# reflow_oven.net
KiCad netlist of a schematic drawn in EAGLE
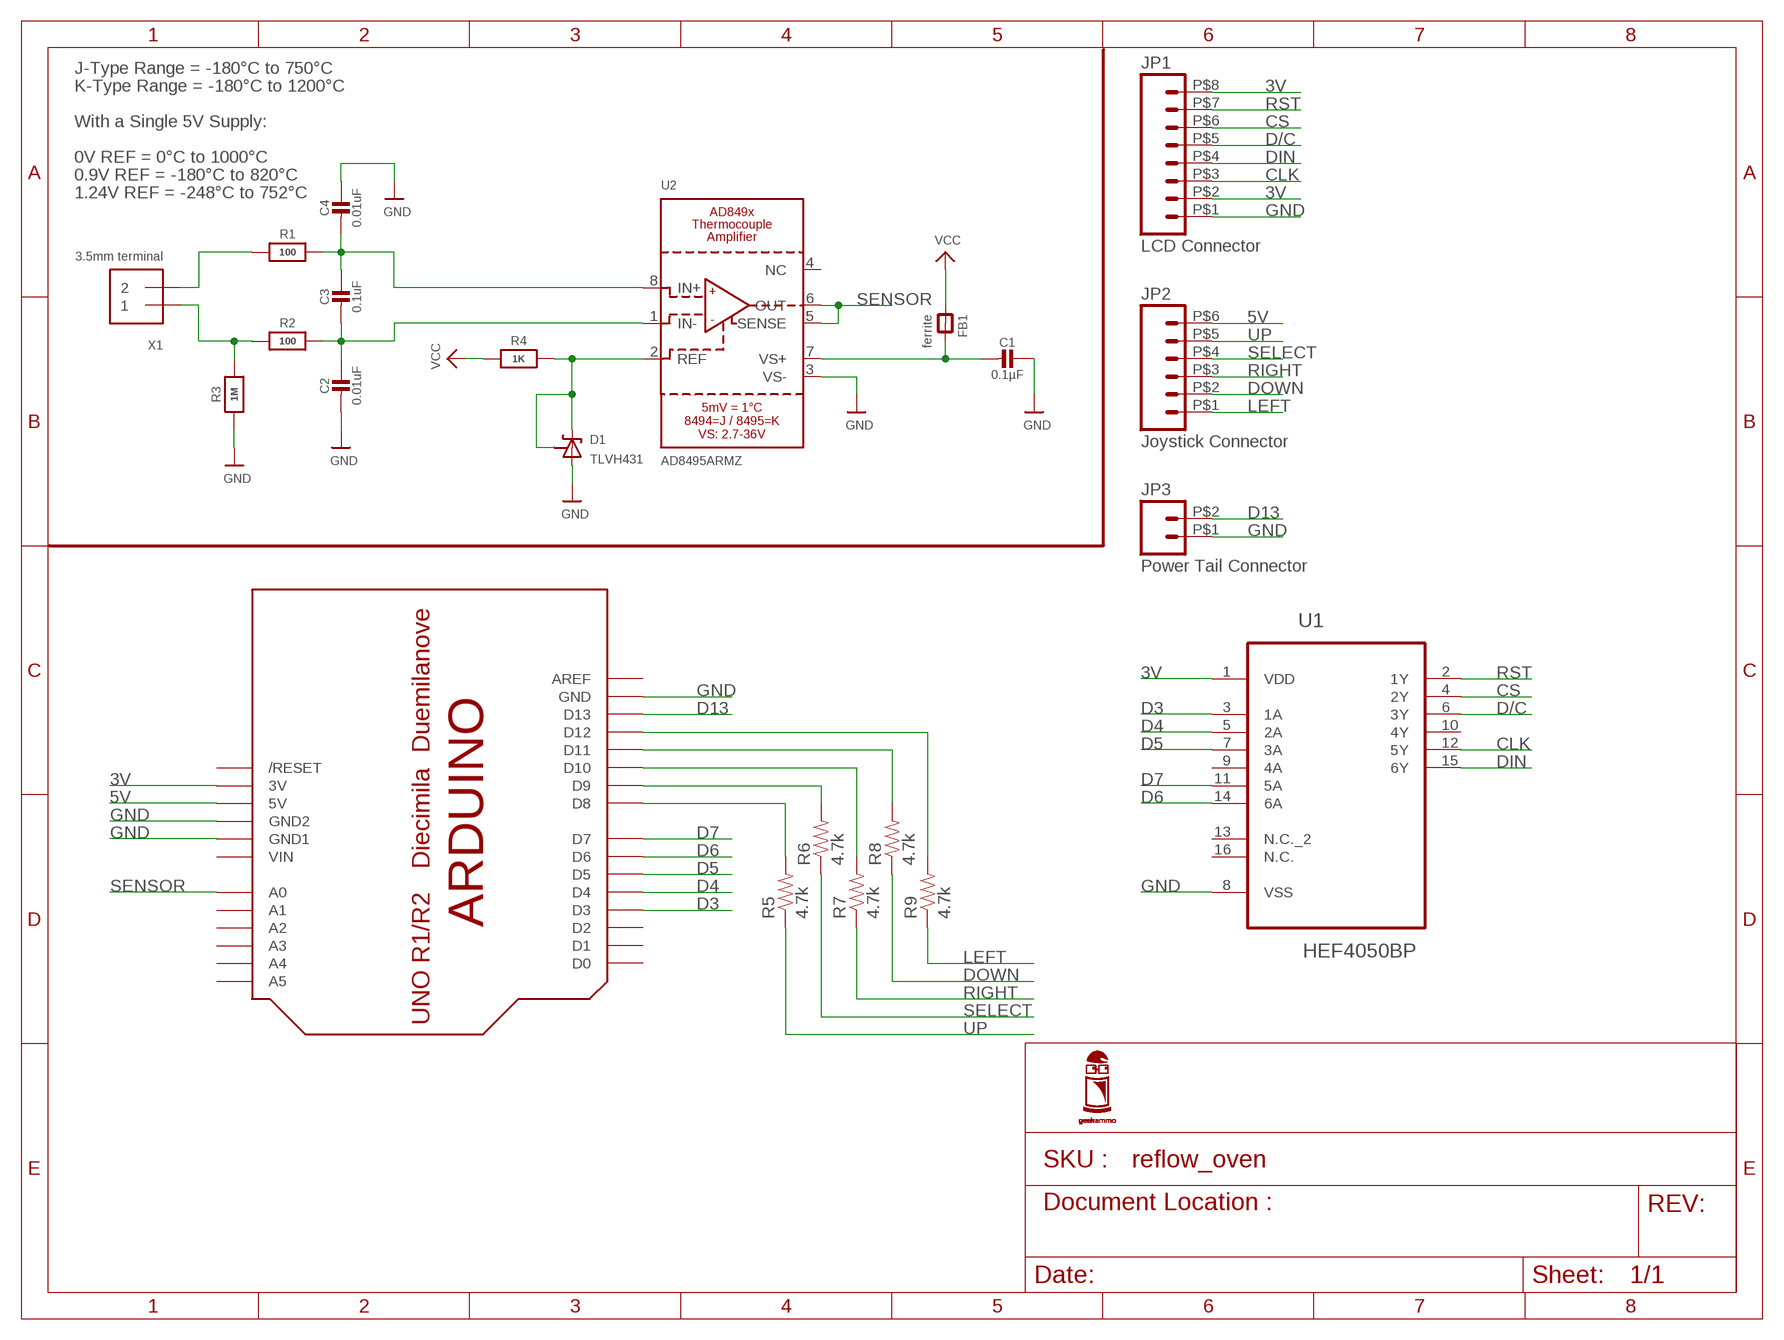
[diagram p0: schematic, sheet 1]

(export (version "E")
  (design (tool "Eeschema 10.0.6"))
  (components
    (comp (ref "C1")
      (value "0.1µF")
      (footprint "eagle-import:0805-NO")
      (libsource (lib "eagle-import") (part "CAP_CERAMIC0805-NOOUTLINE"))
    )
    (comp (ref "C2")
      (value "0.01uF")
      (footprint "eagle-import:0805-NO")
      (libsource (lib "eagle-import") (part "CAP_CERAMIC0805-NOOUTLINE"))
    )
    (comp (ref "C3")
      (value "0.1uF")
      (footprint "eagle-import:0805-NO")
      (libsource (lib "eagle-import") (part "CAP_CERAMIC0805-NOOUTLINE"))
    )
    (comp (ref "C4")
      (value "0.01uF")
      (footprint "eagle-import:0805-NO")
      (libsource (lib "eagle-import") (part "CAP_CERAMIC0805-NOOUTLINE"))
    )
    (comp (ref "D1")
      (value "TLVH431")
      (footprint "eagle-import:SOT23-R")
      (libsource (lib "eagle-import") (part "SHUNT-VREF"))
    )
    (comp (ref "FB1")
      (value "ferrite")
      (footprint "eagle-import:0805")
      (libsource (lib "eagle-import") (part "FERRITE0805"))
    )
    (comp (ref "JP1")
      (value "LCD Connector")
      (footprint "eagle-import:SPRINGTERMINAL-0.1_-8")
      (libsource (lib "eagle-import") (part "M080.1{dblquote}-8"))
    )
    (comp (ref "JP2")
      (value "Joystick Connector")
      (footprint "eagle-import:SPRINGTERMINAL-0.1_-6")
      (libsource (lib "eagle-import") (part "M06"))
    )
    (comp (ref "JP3")
      (value "Power Tail Connector")
      (footprint "eagle-import:SPRINGTERMINAL-0.1_-2")
      (libsource (lib "eagle-import") (part "M02SPRING-0.1{dblquote}"))
    )
    (comp (ref "R1")
      (value "100")
      (footprint "eagle-import:0805-NO")
      (libsource (lib "eagle-import") (part "RESISTOR0805_NOOUTLINE"))
    )
    (comp (ref "R2")
      (value "100")
      (footprint "eagle-import:0805-NO")
      (libsource (lib "eagle-import") (part "RESISTOR0805_NOOUTLINE"))
    )
    (comp (ref "R3")
      (value "1M")
      (footprint "eagle-import:0805-NO")
      (libsource (lib "eagle-import") (part "RESISTOR0805_NOOUTLINE"))
    )
    (comp (ref "R4")
      (value "1K")
      (footprint "eagle-import:0805-NO")
      (libsource (lib "eagle-import") (part "RESISTOR0805_NOOUTLINE"))
    )
    (comp (ref "R5")
      (value "4.7k")
      (footprint "eagle-import:0805")
      (libsource (lib "eagle-import") (part "RESISTOR0805-RES"))
    )
    (comp (ref "R6")
      (value "4.7k")
      (footprint "eagle-import:0805")
      (libsource (lib "eagle-import") (part "RESISTOR0805-RES"))
    )
    (comp (ref "R7")
      (value "4.7k")
      (footprint "eagle-import:0805")
      (libsource (lib "eagle-import") (part "RESISTOR0805-RES"))
    )
    (comp (ref "R8")
      (value "4.7k")
      (footprint "eagle-import:0805")
      (libsource (lib "eagle-import") (part "RESISTOR0805-RES"))
    )
    (comp (ref "R9")
      (value "4.7k")
      (footprint "eagle-import:0805")
      (libsource (lib "eagle-import") (part "RESISTOR0805-RES"))
    )
    (comp (ref "U$1")
      (value "ARDUINOUNO")
      (footprint "eagle-import:ARDUINO")
      (libsource (lib "eagle-import") (part "ARDUINOUNO"))
    )
    (comp (ref "U1")
      (value "HEF4050BP")
      (footprint "eagle-import:DIP254P762X420-16")
      (libsource (lib "eagle-import") (part "HEF4050BP"))
    )
    (comp (ref "U2")
      (value "AD8495ARMZ")
      (footprint "eagle-import:MSOP8_0.65MM")
      (libsource (lib "eagle-import") (part "AD849X"))
    )
    (comp (ref "X1")
      (value "3.5mm terminal")
      (footprint "eagle-import:TERMBLOCK_1X2-3.5MM")
      (libsource (lib "eagle-import") (part "TERMBLOCK_1X2"))
    )
  )
  (nets
    (net (code "1") (name "/3V") (class "Default")
      (node (ref "JP1") (pin "P$2") (pinfunction "2_P$2") (pintype "passive"))
      (node (ref "JP1") (pin "P$8") (pinfunction "8_P$8") (pintype "passive"))
      (node (ref "U$1") (pin "3V") (pinfunction "3V_3V") (pintype "power_in"))
      (node (ref "U1") (pin "1") (pinfunction "VDD_1") (pintype "power_in"))
    )
    (net (code "2") (name "/5V") (class "Default")
      (node (ref "JP2") (pin "P$6") (pinfunction "6_P$6") (pintype "passive"))
      (node (ref "U$1") (pin "5V") (pinfunction "5V_5V") (pintype "power_in"))
    )
    (net (code "3") (name "/CLK") (class "Default")
      (node (ref "JP1") (pin "P$3") (pinfunction "3_P$3") (pintype "passive"))
      (node (ref "U1") (pin "12") (pinfunction "5Y_12") (pintype "output"))
    )
    (net (code "4") (name "/CS") (class "Default")
      (node (ref "JP1") (pin "P$6") (pinfunction "6_P$6") (pintype "passive"))
      (node (ref "U1") (pin "4") (pinfunction "2Y_4") (pintype "output"))
    )
    (net (code "5") (name "/D3") (class "Default")
      (node (ref "U$1") (pin "D3") (pinfunction "D3_D3") (pintype "bidirectional"))
      (node (ref "U1") (pin "3") (pinfunction "1A_3") (pintype "input"))
    )
    (net (code "6") (name "/D4") (class "Default")
      (node (ref "U$1") (pin "D4") (pinfunction "D4_D4") (pintype "bidirectional"))
      (node (ref "U1") (pin "5") (pinfunction "2A_5") (pintype "input"))
    )
    (net (code "7") (name "/D5") (class "Default")
      (node (ref "U$1") (pin "D5") (pinfunction "D5_D5") (pintype "bidirectional"))
      (node (ref "U1") (pin "7") (pinfunction "3A_7") (pintype "input"))
    )
    (net (code "8") (name "/D6") (class "Default")
      (node (ref "U$1") (pin "D6") (pinfunction "D6_D6") (pintype "bidirectional"))
      (node (ref "U1") (pin "14") (pinfunction "6A_14") (pintype "input"))
    )
    (net (code "9") (name "/D7") (class "Default")
      (node (ref "U$1") (pin "D7") (pinfunction "D7_D7") (pintype "bidirectional"))
      (node (ref "U1") (pin "11") (pinfunction "5A_11") (pintype "input"))
    )
    (net (code "10") (name "/D13") (class "Default")
      (node (ref "JP3") (pin "P$2") (pinfunction "2_P$2") (pintype "passive"))
      (node (ref "U$1") (pin "D13") (pinfunction "D13_D13") (pintype "bidirectional"))
    )
    (net (code "11") (name "/DIN") (class "Default")
      (node (ref "JP1") (pin "P$4") (pinfunction "4_P$4") (pintype "passive"))
      (node (ref "U1") (pin "15") (pinfunction "6Y_15") (pintype "output"))
    )
    (net (code "12") (name "/DOWN") (class "Default")
      (node (ref "JP2") (pin "P$2") (pinfunction "2_P$2") (pintype "passive"))
      (node (ref "R8") (pin "1") (pinfunction "1_1") (pintype "passive"))
    )
    (net (code "13") (name "/D{slash}C") (class "Default")
      (node (ref "JP1") (pin "P$5") (pinfunction "5_P$5") (pintype "passive"))
      (node (ref "U1") (pin "6") (pinfunction "3Y_6") (pintype "output"))
    )
    (net (code "14") (name "/LEFT") (class "Default")
      (node (ref "JP2") (pin "P$1") (pinfunction "1_P$1") (pintype "passive"))
      (node (ref "R9") (pin "1") (pinfunction "1_1") (pintype "passive"))
    )
    (net (code "15") (name "/RIGHT") (class "Default")
      (node (ref "JP2") (pin "P$3") (pinfunction "3_P$3") (pintype "passive"))
      (node (ref "R7") (pin "1") (pinfunction "1_1") (pintype "passive"))
    )
    (net (code "16") (name "/RST") (class "Default")
      (node (ref "JP1") (pin "P$7") (pinfunction "7_P$7") (pintype "passive"))
      (node (ref "U1") (pin "2") (pinfunction "1Y_2") (pintype "output"))
    )
    (net (code "17") (name "/SELECT") (class "Default")
      (node (ref "JP2") (pin "P$4") (pinfunction "4_P$4") (pintype "passive"))
      (node (ref "R6") (pin "1") (pinfunction "1_1") (pintype "passive"))
    )
    (net (code "18") (name "/SENSOR") (class "Default")
      (node (ref "U$1") (pin "A0") (pinfunction "A0_A0") (pintype "bidirectional"))
      (node (ref "U2") (pin "5") (pinfunction "SENSE_5") (pintype "bidirectional"))
      (node (ref "U2") (pin "6") (pinfunction "OUT_6") (pintype "output"))
    )
    (net (code "19") (name "/UP") (class "Default")
      (node (ref "JP2") (pin "P$5") (pinfunction "5_P$5") (pintype "passive"))
      (node (ref "R5") (pin "1") (pinfunction "1_1") (pintype "passive"))
    )
    (net (code "20") (name "/VIN") (class "Default")
      (node (ref "U$1") (pin "VIN") (pinfunction "VIN_VIN") (pintype "power_in"))
    )
    (net (code "21") (name "GND") (class "Default")
      (node (ref "C1") (pin "1") (pinfunction "1_1") (pintype "passive"))
      (node (ref "C2") (pin "2") (pinfunction "2_2") (pintype "passive"))
      (node (ref "C4") (pin "1") (pinfunction "1_1") (pintype "passive"))
      (node (ref "D1") (pin "3") (pinfunction "A_3") (pintype "passive"))
      (node (ref "JP1") (pin "P$1") (pinfunction "1_P$1") (pintype "passive"))
      (node (ref "JP3") (pin "P$1") (pinfunction "1_P$1") (pintype "passive"))
      (node (ref "R3") (pin "1") (pinfunction "1_1") (pintype "passive"))
      (node (ref "U$1") (pin "GND") (pinfunction "GND_GND") (pintype "power_in"))
      (node (ref "U$1") (pin "GND1") (pinfunction "GND1_GND1") (pintype "power_in"))
      (node (ref "U$1") (pin "GND2") (pinfunction "GND2_GND2") (pintype "power_in"))
      (node (ref "U1") (pin "8") (pinfunction "VSS_8") (pintype "passive"))
      (node (ref "U2") (pin "3") (pinfunction "VS-_3") (pintype "power_in"))
    )
    (net (code "22") (name "Net-(D1-C)") (class "Default")
      (node (ref "D1") (pin "1") (pinfunction "VREF_1") (pintype "passive"))
      (node (ref "D1") (pin "2") (pinfunction "C_2") (pintype "passive"))
      (node (ref "R4") (pin "2") (pinfunction "2_2") (pintype "passive"))
      (node (ref "U2") (pin "2") (pinfunction "REF_2") (pintype "input"))
    )
    (net (code "23") (name "Net-(FB1-P$2)") (class "Default")
      (node (ref "C1") (pin "2") (pinfunction "2_2") (pintype "passive"))
      (node (ref "FB1") (pin "2") (pinfunction "P$2_2") (pintype "passive"))
      (node (ref "U2") (pin "7") (pinfunction "VS+_7") (pintype "power_in"))
    )
    (net (code "24") (name "Net-(R1-Pad1)") (class "Default")
      (node (ref "R1") (pin "1") (pinfunction "1_1") (pintype "passive"))
      (node (ref "X1") (pin "2") (pinfunction "2_2") (pintype "passive"))
    )
    (net (code "25") (name "Net-(R2-Pad1)") (class "Default")
      (node (ref "R2") (pin "1") (pinfunction "1_1") (pintype "passive"))
      (node (ref "R3") (pin "2") (pinfunction "2_2") (pintype "passive"))
      (node (ref "X1") (pin "1") (pinfunction "1_1") (pintype "passive"))
    )
    (net (code "26") (name "Net-(R5-Pad2)") (class "Default")
      (node (ref "R5") (pin "2") (pinfunction "2_2") (pintype "passive"))
      (node (ref "U$1") (pin "D8") (pinfunction "D8_D8") (pintype "bidirectional"))
    )
    (net (code "27") (name "Net-(R6-Pad2)") (class "Default")
      (node (ref "R6") (pin "2") (pinfunction "2_2") (pintype "passive"))
      (node (ref "U$1") (pin "D9") (pinfunction "D9_D9") (pintype "bidirectional"))
    )
    (net (code "28") (name "Net-(R7-Pad2)") (class "Default")
      (node (ref "R7") (pin "2") (pinfunction "2_2") (pintype "passive"))
      (node (ref "U$1") (pin "D10") (pinfunction "D10_D10") (pintype "bidirectional"))
    )
    (net (code "29") (name "Net-(R8-Pad2)") (class "Default")
      (node (ref "R8") (pin "2") (pinfunction "2_2") (pintype "passive"))
      (node (ref "U$1") (pin "D11") (pinfunction "D11_D11") (pintype "bidirectional"))
    )
    (net (code "30") (name "Net-(R9-Pad2)") (class "Default")
      (node (ref "R9") (pin "2") (pinfunction "2_2") (pintype "passive"))
      (node (ref "U$1") (pin "D12") (pinfunction "D12_D12") (pintype "bidirectional"))
    )
    (net (code "31") (name "Net-(U2-IN+)") (class "Default")
      (node (ref "C3") (pin "1") (pinfunction "1_1") (pintype "passive"))
      (node (ref "C4") (pin "2") (pinfunction "2_2") (pintype "passive"))
      (node (ref "R1") (pin "2") (pinfunction "2_2") (pintype "passive"))
      (node (ref "U2") (pin "8") (pinfunction "IN+_8") (pintype "input"))
    )
    (net (code "32") (name "Net-(U2-IN-)") (class "Default")
      (node (ref "C2") (pin "1") (pinfunction "1_1") (pintype "passive"))
      (node (ref "C3") (pin "2") (pinfunction "2_2") (pintype "passive"))
      (node (ref "R2") (pin "2") (pinfunction "2_2") (pintype "passive"))
      (node (ref "U2") (pin "1") (pinfunction "IN-_1") (pintype "input"))
    )
    (net (code "33") (name "VCC") (class "Default")
      (node (ref "FB1") (pin "1") (pinfunction "P$1_1") (pintype "passive"))
      (node (ref "R4") (pin "1") (pinfunction "1_1") (pintype "passive"))
    )
    (net (code "34") (name "unconnected-(U$1-PadA1)") (class "Default")
      (node (ref "U$1") (pin "A1") (pinfunction "A1_A1") (pintype "bidirectional"))
    )
    (net (code "35") (name "unconnected-(U$1-PadA2)") (class "Default")
      (node (ref "U$1") (pin "A2") (pinfunction "A2_A2") (pintype "bidirectional"))
    )
    (net (code "36") (name "unconnected-(U$1-PadA3)") (class "Default")
      (node (ref "U$1") (pin "A3") (pinfunction "A3_A3") (pintype "bidirectional"))
    )
    (net (code "37") (name "unconnected-(U$1-PadA4)") (class "Default")
      (node (ref "U$1") (pin "A4") (pinfunction "A4_A4") (pintype "bidirectional"))
    )
    (net (code "38") (name "unconnected-(U$1-PadA5)") (class "Default")
      (node (ref "U$1") (pin "A5") (pinfunction "A5_A5") (pintype "bidirectional"))
    )
    (net (code "39") (name "unconnected-(U$1-PadAREF)") (class "Default")
      (node (ref "U$1") (pin "AREF") (pinfunction "AREF_AREF") (pintype "bidirectional"))
    )
    (net (code "40") (name "unconnected-(U$1-PadD0)") (class "Default")
      (node (ref "U$1") (pin "D0") (pinfunction "D0_D0") (pintype "bidirectional"))
    )
    (net (code "41") (name "unconnected-(U$1-PadD1)") (class "Default")
      (node (ref "U$1") (pin "D1") (pinfunction "D1_D1") (pintype "bidirectional"))
    )
    (net (code "42") (name "unconnected-(U$1-PadD2)") (class "Default")
      (node (ref "U$1") (pin "D2") (pinfunction "D2_D2") (pintype "bidirectional"))
    )
    (net (code "43") (name "unconnected-(U$1-{slash}RESET-PadRESET)") (class "Default")
      (node (ref "U$1") (pin "RESET") (pinfunction "/RESET_RESET") (pintype "bidirectional"))
    )
    (net (code "44") (name "unconnected-(U1-4A-Pad9)") (class "Default")
      (node (ref "U1") (pin "9") (pinfunction "4A_9") (pintype "input"))
    )
    (net (code "45") (name "unconnected-(U1-4Y-Pad10)") (class "Default")
      (node (ref "U1") (pin "10") (pinfunction "4Y_10") (pintype "output"))
    )
    (net (code "46") (name "unconnected-(U1-N.C.-Pad16)") (class "Default")
      (node (ref "U1") (pin "16") (pinfunction "N.C._16") (pintype "no_connect"))
    )
    (net (code "47") (name "unconnected-(U1-N.C._2-Pad13)") (class "Default")
      (node (ref "U1") (pin "13") (pinfunction "N.C._2_13") (pintype "no_connect"))
    )
    (net (code "48") (name "unconnected-(U2-NC-Pad4)") (class "Default")
      (node (ref "U2") (pin "4") (pinfunction "NC_4") (pintype "no_connect"))
    )
  )
)
